# vme_can_fpga_conf.net
KiCad netlist of a schematic drawn in Altium Designer
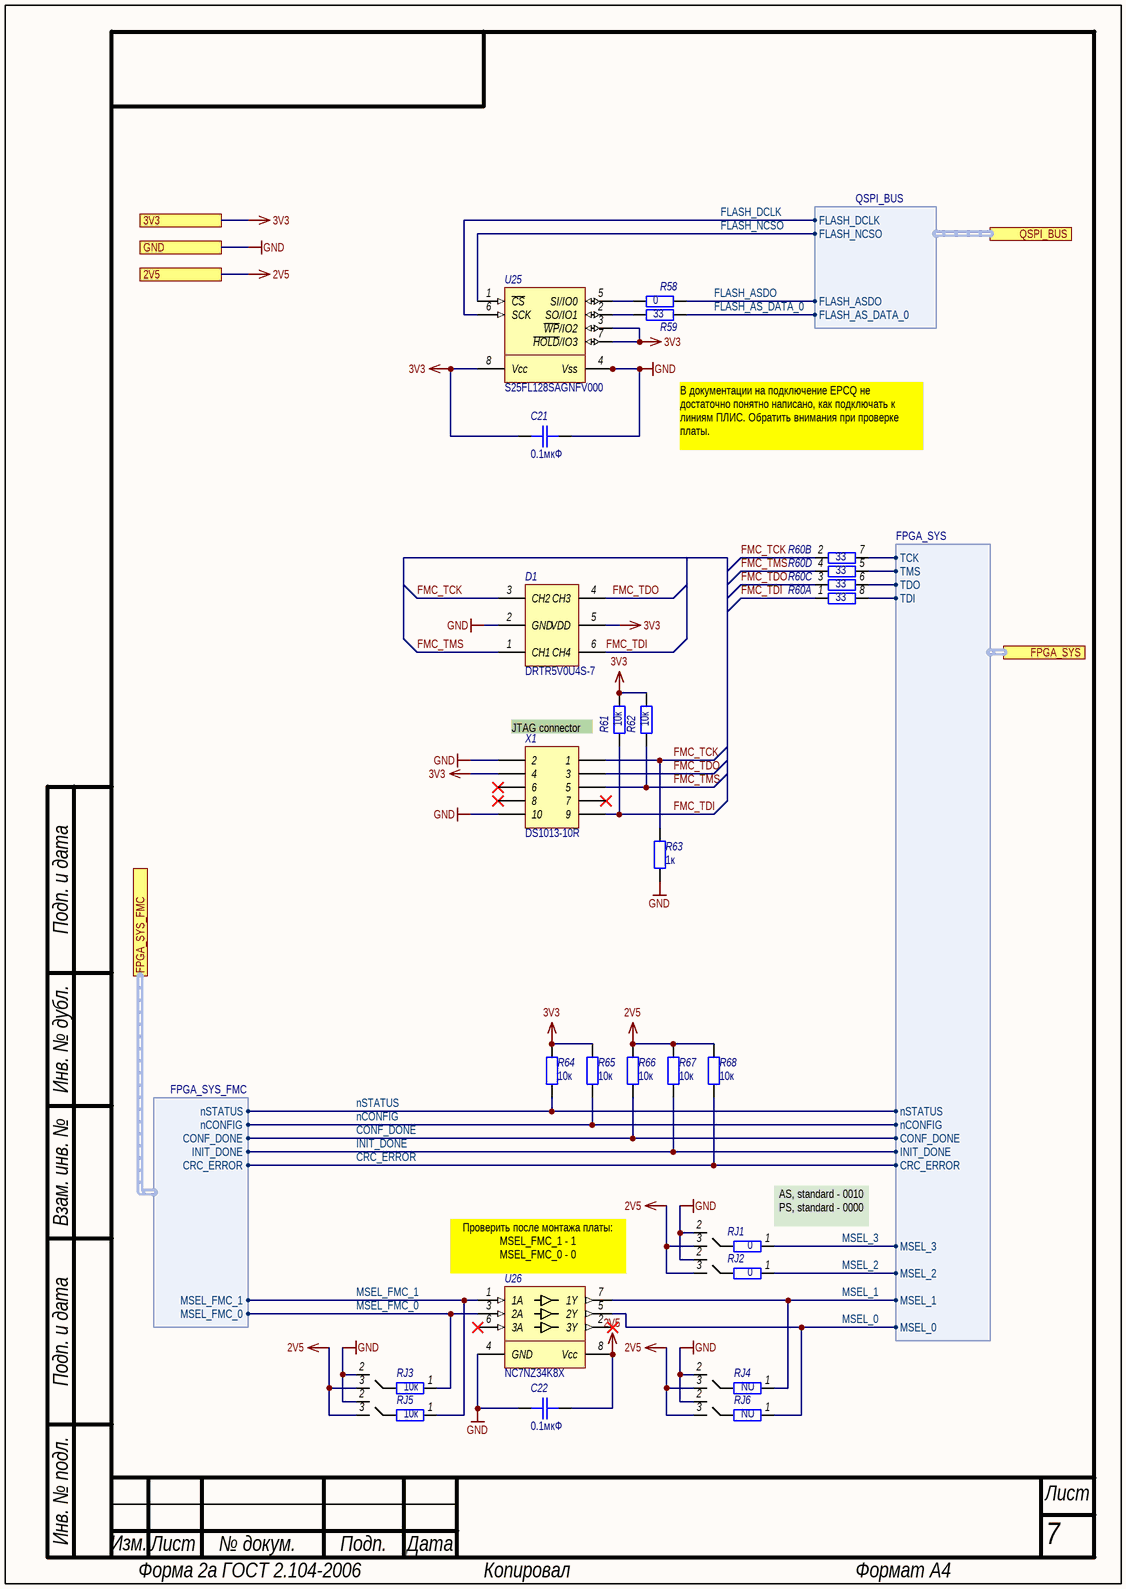
[diagram p0: vme_can_fpga_conf.SchDoc]

(export (version "E")
  (design (tool "Eeschema 10.0.6"))
  (components
    (comp (ref "C21")
      (value "0.1мкФ")
      (footprint "SMD_C0402")
      (description "Capacitor")
      (libsource (lib "Passive") (part "Capacitor"))
    )
    (comp (ref "C22")
      (value "0.1мкФ")
      (footprint "SMD_C0402")
      (description "Capacitor")
      (libsource (lib "Passive") (part "Capacitor"))
    )
    (comp (ref "D1")
      (value "DRTR5V0U4S")
      (footprint "SOT-363")
      (description "4 CHANNEL LOW CAPACITANCE TVS DIODE ARRAY")
      (fields (field (name "НАИМЕНОВАНИЕ") "DRTR5V0U4S-7"))
      (libsource (lib "Diod") (part "DRTR5V0U4S"))
    )
    (comp (ref "R58")
      (value "0")
      (footprint "SMD_0603")
      (description "PE1206DRM470R01L")
      (libsource (lib "") (part "Resistor_1"))
    )
    (comp (ref "R59")
      (value "33")
      (footprint "SMD_0603")
      (description "PE1206DRM470R01L")
      (libsource (lib "") (part "Resistor_1"))
    )
    (comp (ref "R60")
      (value "33")
      (footprint "TC124")
      (description "4 Chip Resistor Array")
      (libsource (lib "Passive") (part "Resistor-4"))
    )
    (comp (ref "R61")
      (value "10к")
      (footprint "SMD_0603")
      (description "Resistor")
      (libsource (lib "Passive") (part "Resistor"))
    )
    (comp (ref "R62")
      (value "10к")
      (footprint "SMD_0603")
      (description "Resistor")
      (libsource (lib "Passive") (part "Resistor"))
    )
    (comp (ref "R63")
      (value "1к")
      (footprint "SMD_0603")
      (description "Resistor")
      (libsource (lib "Passive") (part "Resistor"))
    )
    (comp (ref "R64")
      (value "10к")
      (footprint "SMD_0603")
      (description "Resistor")
      (libsource (lib "Passive") (part "Resistor"))
    )
    (comp (ref "R65")
      (value "10к")
      (footprint "SMD_0603")
      (description "Resistor")
      (libsource (lib "Passive") (part "Resistor"))
    )
    (comp (ref "R66")
      (value "10к")
      (footprint "SMD_0603")
      (description "Resistor")
      (libsource (lib "Passive") (part "Resistor"))
    )
    (comp (ref "R67")
      (value "10к")
      (footprint "SMD_0603")
      (description "Resistor")
      (libsource (lib "Passive") (part "Resistor"))
    )
    (comp (ref "R68")
      (value "10к")
      (footprint "SMD_0603")
      (description "Resistor")
      (libsource (lib "Passive") (part "Resistor"))
    )
    (comp (ref "RJ1")
      (value "0")
      (footprint "SMD_JMP_0603")
      (description "Resistor-Jumper")
      (libsource (lib "Passive") (part "Resistor_Jamper"))
    )
    (comp (ref "RJ2")
      (value "0")
      (footprint "SMD_JMP_0603")
      (description "Resistor-Jumper")
      (libsource (lib "Passive") (part "Resistor_Jamper"))
    )
    (comp (ref "RJ3")
      (value "10к")
      (footprint "SMD_JMP_0603")
      (description "Resistor-Jumper")
      (libsource (lib "Passive") (part "Resistor_Jamper"))
    )
    (comp (ref "RJ4")
      (value "NU")
      (footprint "SMD_JMP_0603")
      (description "Resistor-Jumper")
      (libsource (lib "Passive") (part "Resistor_Jamper"))
    )
    (comp (ref "RJ5")
      (value "10к")
      (footprint "SMD_JMP_0603")
      (description "Resistor-Jumper")
      (libsource (lib "Passive") (part "Resistor_Jamper"))
    )
    (comp (ref "RJ6")
      (value "NU")
      (footprint "SMD_JMP_0603")
      (description "Resistor-Jumper")
      (libsource (lib "Passive") (part "Resistor_Jamper"))
    )
    (comp (ref "U25")
      (value "S25FL128SAGN")
      (footprint "WSON-8_6x8")
      (description "Programmable NOR flash memory")
      (fields (field (name "НАИМЕНОВАНИЕ") "S25FL128SAGNFV000"))
      (libsource (lib "Memory") (part "S25FL128SAGN"))
    )
    (comp (ref "U26")
      (value "NC7NZ34")
      (footprint "US-8")
      (description "TinyLogic UHS Triple Buffer")
      (fields (field (name "НАИМЕНОВАНИЕ") "NC7NZ34K8X"))
      (libsource (lib "Logic") (part "NC7NZ34"))
    )
    (comp (ref "X1")
      (value "DS1013-10R")
      (footprint "DS1013-10R")
      (description "Header, 10-Pin, Dual row")
      (fields (field (name "НАИМЕНОВАНИЕ") "DS1013-10R"))
      (libsource (lib "Connector") (part "Header 2X10"))
    )
  )
  (nets
    (net (code "4") (name "/CONF_DONE") (class "Default")
      (node (ref "R66") (pin "1") (pinfunction "1_1") (pintype "passive"))
    )
    (net (code "5") (name "/CRC_ERROR") (class "Default")
      (node (ref "R68") (pin "1") (pinfunction "1_1") (pintype "passive"))
    )
    (net (code "6") (name "/FLASH_ASDO") (class "Default")
      (node (ref "R58") (pin "2") (pinfunction "2_2") (pintype "passive"))
    )
    (net (code "7") (name "/FLASH_AS_DATA_0") (class "Default")
      (node (ref "R59") (pin "2") (pinfunction "2_2") (pintype "passive"))
    )
    (net (code "8") (name "/FLASH_DCLK") (class "Default")
      (node (ref "U25") (pin "6") (pinfunction "SCK_6") (pintype "input"))
    )
    (net (code "9") (name "/FLASH_NCSO") (class "Default")
      (node (ref "U25") (pin "1") (pinfunction "~{CS}_1") (pintype "input"))
    )
    (net (code "10") (name "/FMC_TCK") (class "Default")
      (node (ref "D1") (pin "3") (pinfunction "СH2_3") (pintype "passive"))
      (node (ref "R60") (pin "2") (pinfunction "2_2") (pintype "passive"))
      (node (ref "R63") (pin "2") (pinfunction "2_2") (pintype "passive"))
      (node (ref "X1") (pin "1") (pinfunction "1_1") (pintype "passive"))
    )
    (net (code "11") (name "/FMC_TDI") (class "Default")
      (node (ref "D1") (pin "6") (pinfunction "СH4_6") (pintype "passive"))
      (node (ref "R60") (pin "1") (pinfunction "1_1") (pintype "passive"))
      (node (ref "R61") (pin "1") (pinfunction "1_1") (pintype "passive"))
      (node (ref "X1") (pin "9") (pinfunction "9_9") (pintype "passive"))
    )
    (net (code "12") (name "/FMC_TDO") (class "Default")
      (node (ref "D1") (pin "4") (pinfunction "СH3_4") (pintype "passive"))
      (node (ref "R60") (pin "3") (pinfunction "3_3") (pintype "passive"))
      (node (ref "X1") (pin "3") (pinfunction "3_3") (pintype "passive"))
    )
    (net (code "13") (name "/FMC_TMS") (class "Default")
      (node (ref "D1") (pin "1") (pinfunction "СH1_1") (pintype "passive"))
      (node (ref "R60") (pin "4") (pinfunction "4_4") (pintype "passive"))
      (node (ref "R62") (pin "1") (pinfunction "1_1") (pintype "passive"))
      (node (ref "X1") (pin "5") (pinfunction "5_5") (pintype "passive"))
    )
    (net (code "14") (name "/INIT_DONE") (class "Default")
      (node (ref "R67") (pin "1") (pinfunction "1_1") (pintype "passive"))
    )
    (net (code "15") (name "/MSEL_0") (class "Default")
      (node (ref "RJ6") (pin "1") (pintype "passive"))
      (node (ref "U26") (pin "5") (pinfunction "2Y_5") (pintype "output"))
    )
    (net (code "16") (name "/MSEL_1") (class "Default")
      (node (ref "RJ4") (pin "1") (pintype "passive"))
      (node (ref "U26") (pin "7") (pinfunction "1Y_7") (pintype "output"))
    )
    (net (code "17") (name "/MSEL_2") (class "Default") (node (ref "RJ2") (pin "1") (pintype "passive")))
    (net (code "18") (name "/MSEL_3") (class "Default") (node (ref "RJ1") (pin "1") (pintype "passive")))
    (net (code "19") (name "/MSEL_FMC_0") (class "Default")
      (node (ref "RJ3") (pin "1") (pintype "passive"))
      (node (ref "U26") (pin "3") (pinfunction "2A_3") (pintype "input"))
    )
    (net (code "20") (name "/MSEL_FMC_1") (class "Default")
      (node (ref "RJ5") (pin "1") (pintype "passive"))
      (node (ref "U26") (pin "1") (pinfunction "1A_1") (pintype "input"))
    )
    (net (code "21") (name "/TCK") (class "Default")
      (node (ref "R60") (pin "7") (pinfunction "7_7") (pintype "passive"))
    )
    (net (code "22") (name "/TDI") (class "Default")
      (node (ref "R60") (pin "8") (pinfunction "8_8") (pintype "passive"))
    )
    (net (code "23") (name "/TDO") (class "Default")
      (node (ref "R60") (pin "6") (pinfunction "6_6") (pintype "passive"))
    )
    (net (code "24") (name "/TMS") (class "Default")
      (node (ref "R60") (pin "5") (pinfunction "5_5") (pintype "passive"))
    )
    (net (code "25") (name "/nCONFIG") (class "Default")
      (node (ref "R65") (pin "1") (pinfunction "1_1") (pintype "passive"))
    )
    (net (code "26") (name "/nSTATUS") (class "Default")
      (node (ref "R64") (pin "1") (pinfunction "1_1") (pintype "passive"))
    )
    (net (code "30") (name "2V5") (class "Default")
      (node (ref "C22") (pin "2") (pinfunction "2_2") (pintype "passive"))
      (node (ref "R66") (pin "2") (pinfunction "2_2") (pintype "passive"))
      (node (ref "R67") (pin "2") (pinfunction "2_2") (pintype "passive"))
      (node (ref "R68") (pin "2") (pinfunction "2_2") (pintype "passive"))
      (node (ref "RJ1") (pin "3") (pintype "passive"))
      (node (ref "RJ2") (pin "3") (pintype "passive"))
      (node (ref "RJ3") (pin "3") (pintype "passive"))
      (node (ref "RJ4") (pin "3") (pintype "passive"))
      (node (ref "RJ5") (pin "3") (pintype "passive"))
      (node (ref "RJ6") (pin "3") (pintype "passive"))
      (node (ref "U26") (pin "8") (pinfunction "Vcc_8") (pintype "power_in"))
    )
    (net (code "31") (name "3V3") (class "Default")
      (node (ref "C21") (pin "2") (pinfunction "2_2") (pintype "passive"))
      (node (ref "D1") (pin "5") (pinfunction "VDD_5") (pintype "power_in"))
      (node (ref "R61") (pin "2") (pinfunction "2_2") (pintype "passive"))
      (node (ref "R62") (pin "2") (pinfunction "2_2") (pintype "passive"))
      (node (ref "R64") (pin "2") (pinfunction "2_2") (pintype "passive"))
      (node (ref "R65") (pin "2") (pinfunction "2_2") (pintype "passive"))
      (node (ref "U25") (pin "3") (pinfunction "~{WP}/IO2_3") (pintype "bidirectional"))
      (node (ref "U25") (pin "7") (pinfunction "~{HOLD}/IO3_7") (pintype "bidirectional"))
      (node (ref "U25") (pin "8") (pinfunction "Vcc_8") (pintype "power_in"))
      (node (ref "X1") (pin "4") (pinfunction "4_4") (pintype "passive"))
    )
    (net (code "32") (name "GND") (class "Default")
      (node (ref "C21") (pin "1") (pinfunction "1_1") (pintype "passive"))
      (node (ref "C22") (pin "1") (pinfunction "1_1") (pintype "passive"))
      (node (ref "D1") (pin "2") (pinfunction "GND_2") (pintype "power_in"))
      (node (ref "R63") (pin "1") (pinfunction "1_1") (pintype "passive"))
      (node (ref "RJ1") (pin "2") (pintype "passive"))
      (node (ref "RJ2") (pin "2") (pintype "passive"))
      (node (ref "RJ3") (pin "2") (pintype "passive"))
      (node (ref "RJ4") (pin "2") (pintype "passive"))
      (node (ref "RJ5") (pin "2") (pintype "passive"))
      (node (ref "RJ6") (pin "2") (pintype "passive"))
      (node (ref "U25") (pin "4") (pinfunction "Vss_4") (pintype "power_in"))
      (node (ref "U25") (pin "9") (pinfunction "TP_9") (pintype "power_in"))
      (node (ref "U26") (pin "4") (pinfunction "GND_4") (pintype "power_in"))
      (node (ref "X1") (pin "10") (pinfunction "10_10") (pintype "passive"))
      (node (ref "X1") (pin "2") (pinfunction "2_2") (pintype "passive"))
    )
    (net (code "33") (name "Net-(U25-SI{slash}IO0)") (class "Default")
      (node (ref "R58") (pin "1") (pinfunction "1_1") (pintype "passive"))
      (node (ref "U25") (pin "5") (pinfunction "SI/IO0_5") (pintype "bidirectional"))
    )
    (net (code "34") (name "Net-(U25-SO{slash}IO1)") (class "Default")
      (node (ref "R59") (pin "1") (pinfunction "1_1") (pintype "passive"))
      (node (ref "U25") (pin "2") (pinfunction "SO/IO1_2") (pintype "bidirectional"))
    )
    (net (code "35") (name "unconnected-(U26-3A-Pad6)") (class "Default")
      (node (ref "U26") (pin "6") (pinfunction "3A_6") (pintype "input+no_connect"))
    )
    (net (code "36") (name "unconnected-(U26-3Y-Pad2)") (class "Default")
      (node (ref "U26") (pin "2") (pinfunction "3Y_2") (pintype "output+no_connect"))
    )
    (net (code "37") (name "unconnected-(X1-Pad6)") (class "Default")
      (node (ref "X1") (pin "6") (pinfunction "6_6") (pintype "passive+no_connect"))
    )
    (net (code "38") (name "unconnected-(X1-Pad7)") (class "Default")
      (node (ref "X1") (pin "7") (pinfunction "7_7") (pintype "passive+no_connect"))
    )
    (net (code "39") (name "unconnected-(X1-Pad8)") (class "Default")
      (node (ref "X1") (pin "8") (pinfunction "8_8") (pintype "passive+no_connect"))
    )
  )
)
